# Relais.net
KiCad netlist of a schematic drawn in EAGLE
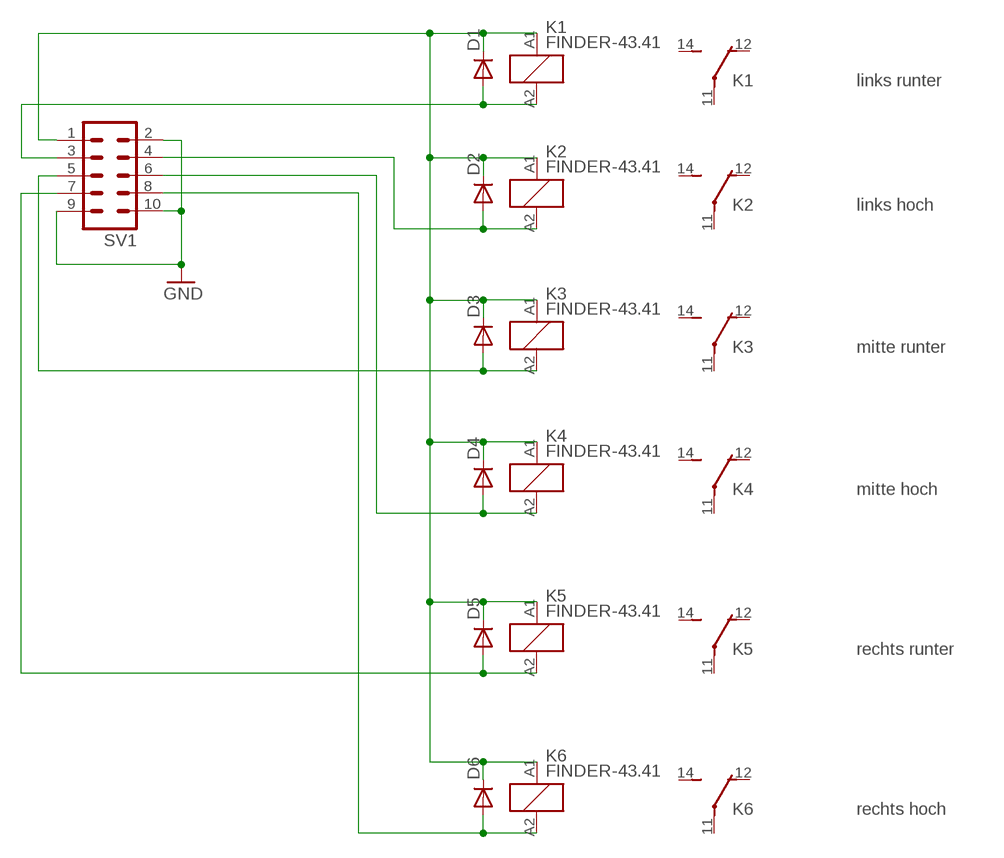
[diagram p0: schematic, sheet 1]

(export (version "E")
  (design (tool "Eeschema 10.0.6"))
  (components
    (comp (ref "D1")
      (value "DIODE-D-7.5")
      (footprint "eagle-import:D-7.5")
      (libsource (lib "eagle-import") (part "DIODE-D-7.5"))
    )
    (comp (ref "D2")
      (value "DIODE-D-7.5")
      (footprint "eagle-import:D-7.5")
      (libsource (lib "eagle-import") (part "DIODE-D-7.5"))
    )
    (comp (ref "D3")
      (value "DIODE-D-7.5")
      (footprint "eagle-import:D-7.5")
      (libsource (lib "eagle-import") (part "DIODE-D-7.5"))
    )
    (comp (ref "D4")
      (value "DIODE-D-7.5")
      (footprint "eagle-import:D-7.5")
      (libsource (lib "eagle-import") (part "DIODE-D-7.5"))
    )
    (comp (ref "D5")
      (value "DIODE-D-7.5")
      (footprint "eagle-import:D-7.5")
      (libsource (lib "eagle-import") (part "DIODE-D-7.5"))
    )
    (comp (ref "D6")
      (value "DIODE-D-7.5")
      (footprint "eagle-import:D-7.5")
      (libsource (lib "eagle-import") (part "DIODE-D-7.5"))
    )
    (comp (ref "K1")
      (value "FINDER-43.41")
      (footprint "eagle-import:FINDER-43.41")
      (libsource (lib "eagle-import") (part "FINDER-43.41"))
    )
    (comp (ref "K2")
      (value "FINDER-43.41")
      (footprint "eagle-import:FINDER-43.41")
      (libsource (lib "eagle-import") (part "FINDER-43.41"))
    )
    (comp (ref "K3")
      (value "FINDER-43.41")
      (footprint "eagle-import:FINDER-43.41")
      (libsource (lib "eagle-import") (part "FINDER-43.41"))
    )
    (comp (ref "K4")
      (value "FINDER-43.41")
      (footprint "eagle-import:FINDER-43.41")
      (libsource (lib "eagle-import") (part "FINDER-43.41"))
    )
    (comp (ref "K5")
      (value "FINDER-43.41")
      (footprint "eagle-import:FINDER-43.41")
      (libsource (lib "eagle-import") (part "FINDER-43.41"))
    )
    (comp (ref "K6")
      (value "FINDER-43.41")
      (footprint "eagle-import:FINDER-43.41")
      (libsource (lib "eagle-import") (part "FINDER-43.41"))
    )
    (comp (ref "SV1")
      (value "ML10")
      (footprint "eagle-import:ML10")
      (libsource (lib "eagle-import") (part "ML10"))
    )
  )
  (nets
    (net (code "1") (name "GND") (class "Default")
      (node (ref "SV1") (pin "10") (pinfunction "10_10") (pintype "passive"))
      (node (ref "SV1") (pin "2") (pinfunction "2_2") (pintype "passive"))
      (node (ref "SV1") (pin "9") (pinfunction "9_9") (pintype "passive"))
    )
    (net (code "2") (name "Net-(K1B-1)") (class "Default")
      (node (ref "D1") (pin "C") (pinfunction "C_C") (pintype "passive"))
      (node (ref "D2") (pin "C") (pinfunction "C_C") (pintype "passive"))
      (node (ref "D3") (pin "C") (pinfunction "C_C") (pintype "passive"))
      (node (ref "D4") (pin "C") (pinfunction "C_C") (pintype "passive"))
      (node (ref "D5") (pin "C") (pinfunction "C_C") (pintype "passive"))
      (node (ref "D6") (pin "C") (pinfunction "C_C") (pintype "passive"))
      (node (ref "K1") (pin "A1") (pinfunction "1_A1") (pintype "passive"))
      (node (ref "K2") (pin "A1") (pinfunction "1_A1") (pintype "passive"))
      (node (ref "K3") (pin "A1") (pinfunction "1_A1") (pintype "passive"))
      (node (ref "K4") (pin "A1") (pinfunction "1_A1") (pintype "passive"))
      (node (ref "K5") (pin "A1") (pinfunction "1_A1") (pintype "passive"))
      (node (ref "K6") (pin "A1") (pinfunction "1_A1") (pintype "passive"))
      (node (ref "SV1") (pin "1") (pinfunction "1_1") (pintype "passive"))
    )
    (net (code "3") (name "Net-(K1B-2)") (class "Default")
      (node (ref "D1") (pin "A") (pinfunction "A_A") (pintype "passive"))
      (node (ref "K1") (pin "A2") (pinfunction "2_A2") (pintype "passive"))
      (node (ref "SV1") (pin "3") (pinfunction "3_3") (pintype "passive"))
    )
    (net (code "4") (name "Net-(K2B-2)") (class "Default")
      (node (ref "D2") (pin "A") (pinfunction "A_A") (pintype "passive"))
      (node (ref "K2") (pin "A2") (pinfunction "2_A2") (pintype "passive"))
      (node (ref "SV1") (pin "4") (pinfunction "4_4") (pintype "passive"))
    )
    (net (code "5") (name "Net-(K3B-2)") (class "Default")
      (node (ref "D3") (pin "A") (pinfunction "A_A") (pintype "passive"))
      (node (ref "K3") (pin "A2") (pinfunction "2_A2") (pintype "passive"))
      (node (ref "SV1") (pin "5") (pinfunction "5_5") (pintype "passive"))
    )
    (net (code "6") (name "Net-(K4B-2)") (class "Default")
      (node (ref "D4") (pin "A") (pinfunction "A_A") (pintype "passive"))
      (node (ref "K4") (pin "A2") (pinfunction "2_A2") (pintype "passive"))
      (node (ref "SV1") (pin "6") (pinfunction "6_6") (pintype "passive"))
    )
    (net (code "7") (name "Net-(K5B-2)") (class "Default")
      (node (ref "D5") (pin "A") (pinfunction "A_A") (pintype "passive"))
      (node (ref "K5") (pin "A2") (pinfunction "2_A2") (pintype "passive"))
      (node (ref "SV1") (pin "7") (pinfunction "7_7") (pintype "passive"))
    )
    (net (code "8") (name "Net-(K6B-2)") (class "Default")
      (node (ref "D6") (pin "A") (pinfunction "A_A") (pintype "passive"))
      (node (ref "K6") (pin "A2") (pinfunction "2_A2") (pintype "passive"))
      (node (ref "SV1") (pin "8") (pinfunction "8_8") (pintype "passive"))
    )
    (net (code "9") (name "unconnected-(K1A-O-Pad12)") (class "Default")
      (node (ref "K1") (pin "12") (pinfunction "O_12") (pintype "passive"))
    )
    (net (code "10") (name "unconnected-(K1A-P-Pad11)") (class "Default")
      (node (ref "K1") (pin "11") (pinfunction "P_11") (pintype "passive"))
    )
    (net (code "11") (name "unconnected-(K1A-S-Pad14)") (class "Default")
      (node (ref "K1") (pin "14") (pinfunction "S_14") (pintype "passive"))
    )
    (net (code "12") (name "unconnected-(K2A-O-Pad12)") (class "Default")
      (node (ref "K2") (pin "12") (pinfunction "O_12") (pintype "passive"))
    )
    (net (code "13") (name "unconnected-(K2A-P-Pad11)") (class "Default")
      (node (ref "K2") (pin "11") (pinfunction "P_11") (pintype "passive"))
    )
    (net (code "14") (name "unconnected-(K2A-S-Pad14)") (class "Default")
      (node (ref "K2") (pin "14") (pinfunction "S_14") (pintype "passive"))
    )
    (net (code "15") (name "unconnected-(K3A-O-Pad12)") (class "Default")
      (node (ref "K3") (pin "12") (pinfunction "O_12") (pintype "passive"))
    )
    (net (code "16") (name "unconnected-(K3A-P-Pad11)") (class "Default")
      (node (ref "K3") (pin "11") (pinfunction "P_11") (pintype "passive"))
    )
    (net (code "17") (name "unconnected-(K3A-S-Pad14)") (class "Default")
      (node (ref "K3") (pin "14") (pinfunction "S_14") (pintype "passive"))
    )
    (net (code "18") (name "unconnected-(K4A-O-Pad12)") (class "Default")
      (node (ref "K4") (pin "12") (pinfunction "O_12") (pintype "passive"))
    )
    (net (code "19") (name "unconnected-(K4A-P-Pad11)") (class "Default")
      (node (ref "K4") (pin "11") (pinfunction "P_11") (pintype "passive"))
    )
    (net (code "20") (name "unconnected-(K4A-S-Pad14)") (class "Default")
      (node (ref "K4") (pin "14") (pinfunction "S_14") (pintype "passive"))
    )
    (net (code "21") (name "unconnected-(K5A-O-Pad12)") (class "Default")
      (node (ref "K5") (pin "12") (pinfunction "O_12") (pintype "passive"))
    )
    (net (code "22") (name "unconnected-(K5A-P-Pad11)") (class "Default")
      (node (ref "K5") (pin "11") (pinfunction "P_11") (pintype "passive"))
    )
    (net (code "23") (name "unconnected-(K5A-S-Pad14)") (class "Default")
      (node (ref "K5") (pin "14") (pinfunction "S_14") (pintype "passive"))
    )
    (net (code "24") (name "unconnected-(K6A-O-Pad12)") (class "Default")
      (node (ref "K6") (pin "12") (pinfunction "O_12") (pintype "passive"))
    )
    (net (code "25") (name "unconnected-(K6A-P-Pad11)") (class "Default")
      (node (ref "K6") (pin "11") (pinfunction "P_11") (pintype "passive"))
    )
    (net (code "26") (name "unconnected-(K6A-S-Pad14)") (class "Default")
      (node (ref "K6") (pin "14") (pinfunction "S_14") (pintype "passive"))
    )
  )
)
